# buggym2017_condensed.net
KiCad netlist of a schematic drawn in EAGLE
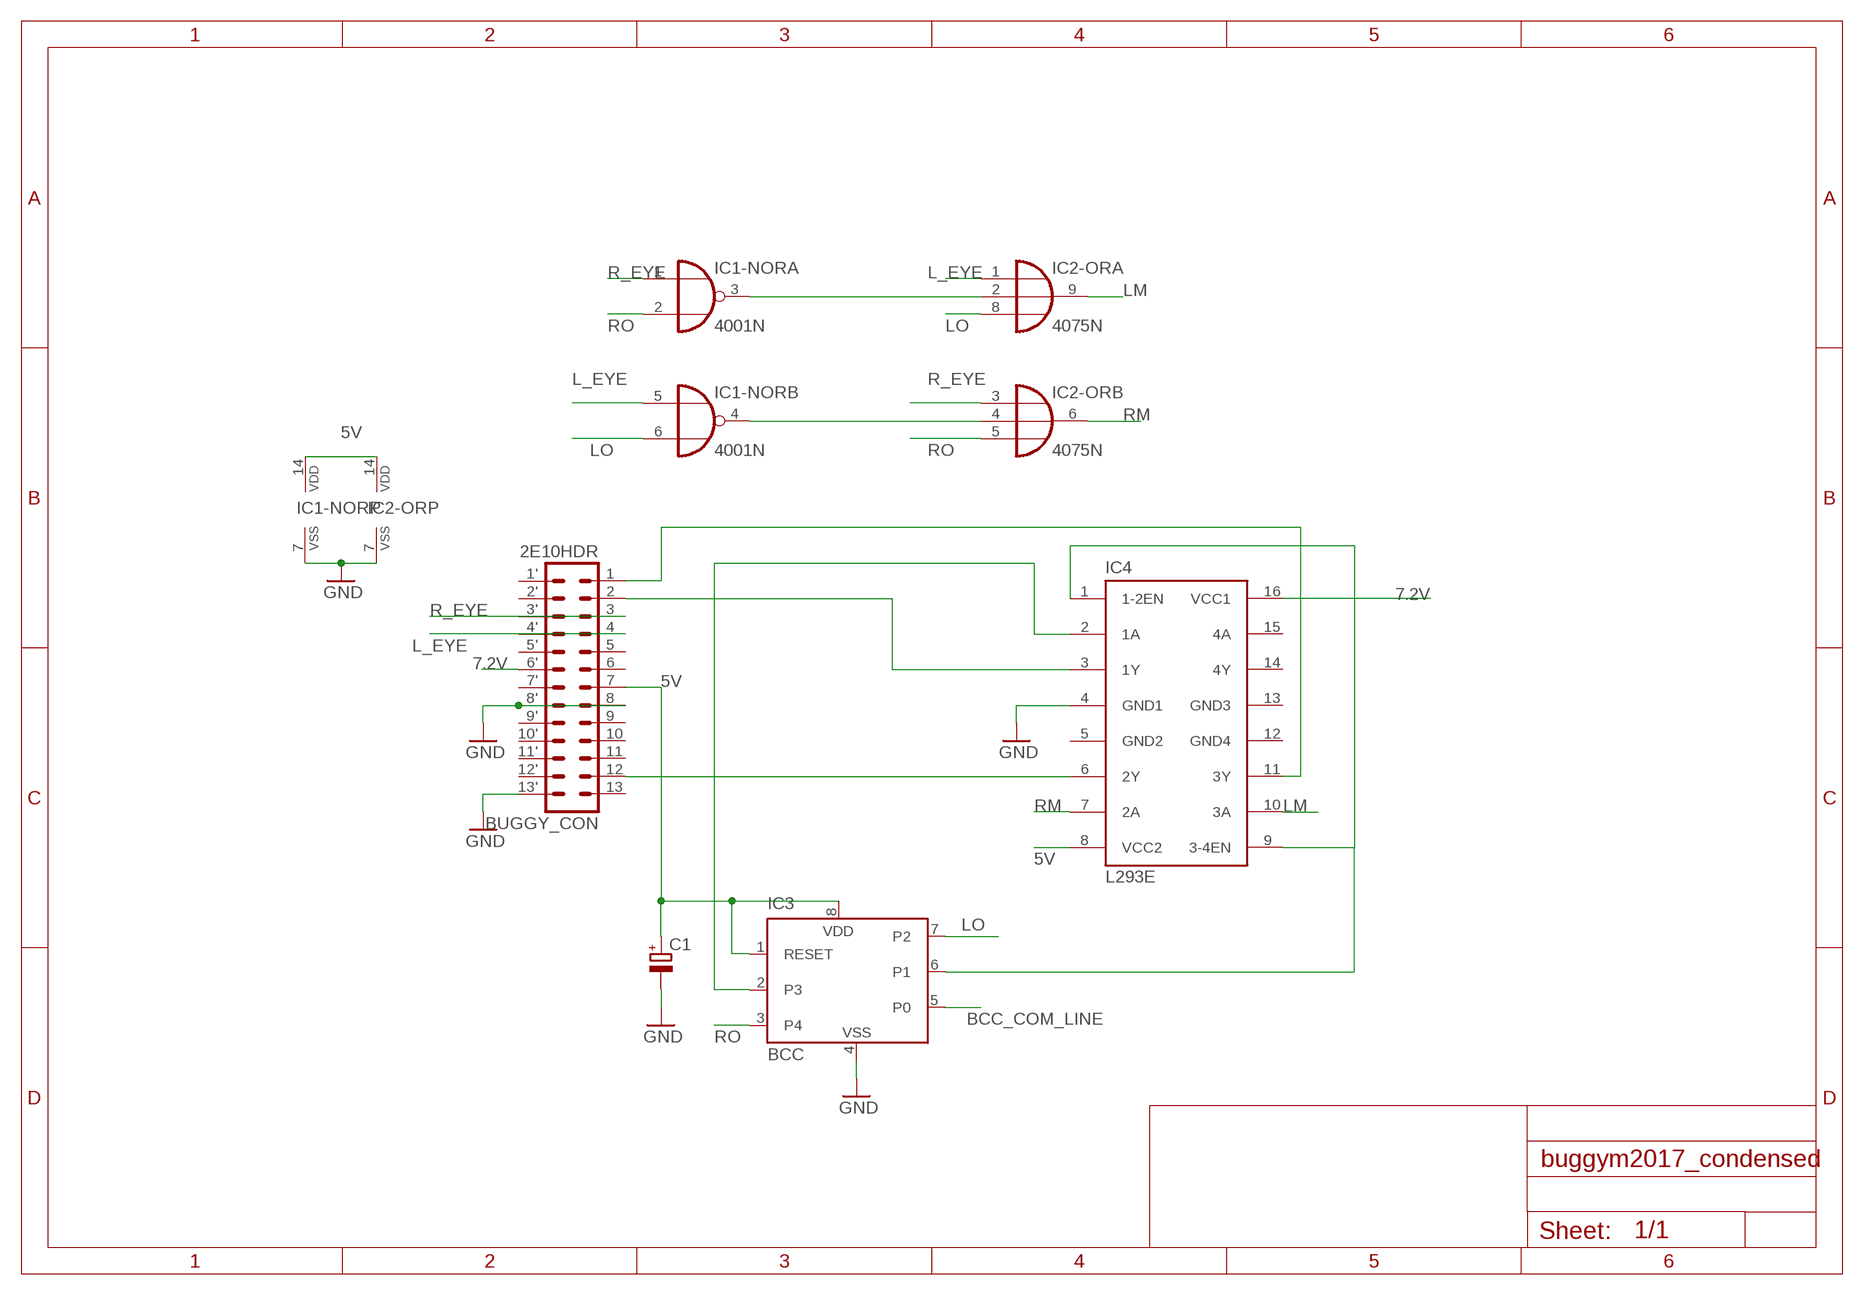
[diagram p0: schematic, sheet 1]

(export (version "E")
  (design (tool "Eeschema 10.0.6"))
  (components
    (comp (ref "BUGGY_CON")
      (value "2E10HDR")
      (footprint "eagle-import:2E10BOARD")
      (libsource (lib "eagle-import") (part "2E10HDR"))
    )
    (comp (ref "C1")
      (value "CPOL-EUE5-4")
      (footprint "eagle-import:E5-4")
      (libsource (lib "eagle-import") (part "CPOL-EUE5-4"))
    )
    (comp (ref "IC1-NOR")
      (value "4001N")
      (footprint "eagle-import:DIL14")
      (libsource (lib "eagle-import") (part "4001N"))
    )
    (comp (ref "IC2-OR")
      (value "4075N")
      (footprint "eagle-import:DIL14")
      (libsource (lib "eagle-import") (part "4075N"))
    )
    (comp (ref "IC3")
      (value "BCC")
      (footprint "eagle-import:DIL8")
      (libsource (lib "eagle-import") (part "BCC"))
    )
    (comp (ref "IC4")
      (value "L293E")
      (footprint "eagle-import:DIL16")
      (fields (field (name "MF") "Arrow Electronics"))
      (libsource (lib "eagle-import") (part "L293E"))
    )
  )
  (nets
    (net (code "1") (name "/5V") (class "Default")
      (node (ref "BUGGY_CON") (pin "7") (pinfunction "7_7") (pintype "passive"))
      (node (ref "C1") (pin "+") (pinfunction "+_+") (pintype "passive"))
      (node (ref "IC1-NOR") (pin "14") (pinfunction "VDD_14") (pintype "power_in"))
      (node (ref "IC2-OR") (pin "14") (pinfunction "VDD_14") (pintype "power_in"))
      (node (ref "IC3") (pin "1") (pinfunction "RESET_1") (pintype "bidirectional"))
      (node (ref "IC3") (pin "8") (pinfunction "5V_8") (pintype "power_in"))
      (node (ref "IC4") (pin "8") (pinfunction "VCC2_8") (pintype "power_in"))
    )
    (net (code "2") (name "/7.2V") (class "Default")
      (node (ref "BUGGY_CON") (pin "6'") (pinfunction "6'_6'") (pintype "passive"))
      (node (ref "IC4") (pin "16") (pinfunction "VCC1_16") (pintype "power_in"))
    )
    (net (code "3") (name "/BCC_COM_LINE") (class "Default")
      (node (ref "IC3") (pin "5") (pinfunction "P0_5") (pintype "bidirectional"))
    )
    (net (code "4") (name "/GND2") (class "Default")
      (node (ref "IC4") (pin "5") (pinfunction "GND2_5") (pintype "power_in"))
    )
    (net (code "5") (name "/GND3") (class "Default")
      (node (ref "IC4") (pin "13") (pinfunction "GND3_13") (pintype "power_in"))
    )
    (net (code "6") (name "/GND4") (class "Default")
      (node (ref "IC4") (pin "12") (pinfunction "GND4_12") (pintype "power_in"))
    )
    (net (code "7") (name "/LM") (class "Default")
      (node (ref "IC2-OR") (pin "9") (pinfunction "O_9") (pintype "output"))
      (node (ref "IC4") (pin "10") (pinfunction "3A_10") (pintype "input"))
    )
    (net (code "8") (name "/LO") (class "Default")
      (node (ref "IC1-NOR") (pin "6") (pinfunction "I1_6") (pintype "input"))
      (node (ref "IC2-OR") (pin "8") (pinfunction "I2_8") (pintype "input"))
      (node (ref "IC3") (pin "7") (pinfunction "P2_7") (pintype "bidirectional"))
    )
    (net (code "9") (name "/L_EYE") (class "Default")
      (node (ref "BUGGY_CON") (pin "4") (pinfunction "4_4") (pintype "passive"))
      (node (ref "BUGGY_CON") (pin "4'") (pinfunction "4'_4'") (pintype "passive"))
      (node (ref "IC1-NOR") (pin "5") (pinfunction "I0_5") (pintype "input"))
      (node (ref "IC2-OR") (pin "1") (pinfunction "I0_1") (pintype "input"))
    )
    (net (code "10") (name "/RM") (class "Default")
      (node (ref "IC2-OR") (pin "6") (pinfunction "O_6") (pintype "output"))
      (node (ref "IC4") (pin "7") (pinfunction "2A_7") (pintype "input"))
    )
    (net (code "11") (name "/RO") (class "Default")
      (node (ref "IC1-NOR") (pin "2") (pinfunction "I1_2") (pintype "input"))
      (node (ref "IC2-OR") (pin "5") (pinfunction "I2_5") (pintype "input"))
      (node (ref "IC3") (pin "3") (pinfunction "P4_3") (pintype "input"))
    )
    (net (code "12") (name "/R_EYE") (class "Default")
      (node (ref "BUGGY_CON") (pin "3") (pinfunction "3_3") (pintype "passive"))
      (node (ref "BUGGY_CON") (pin "3'") (pinfunction "3'_3'") (pintype "passive"))
      (node (ref "IC1-NOR") (pin "1") (pinfunction "I0_1") (pintype "input"))
      (node (ref "IC2-OR") (pin "3") (pinfunction "I0_3") (pintype "input"))
    )
    (net (code "13") (name "GND") (class "Default")
      (node (ref "BUGGY_CON") (pin "13'") (pinfunction "13'_13'") (pintype "passive"))
      (node (ref "BUGGY_CON") (pin "8") (pinfunction "8_8") (pintype "passive"))
      (node (ref "BUGGY_CON") (pin "8'") (pinfunction "8'_8'") (pintype "passive"))
      (node (ref "C1") (pin "-") (pinfunction "-_-") (pintype "passive"))
      (node (ref "IC1-NOR") (pin "7") (pinfunction "VSS_7") (pintype "power_in"))
      (node (ref "IC2-OR") (pin "7") (pinfunction "VSS_7") (pintype "power_in"))
      (node (ref "IC3") (pin "4") (pinfunction "VSS_4") (pintype "power_in"))
      (node (ref "IC4") (pin "4") (pinfunction "GND1_4") (pintype "power_in"))
    )
    (net (code "14") (name "Net-(IC1-NORA-O)") (class "Default")
      (node (ref "IC1-NOR") (pin "3") (pinfunction "O_3") (pintype "output"))
      (node (ref "IC2-OR") (pin "2") (pinfunction "I1_2") (pintype "input"))
    )
    (net (code "15") (name "Net-(IC1-NORB-O)") (class "Default")
      (node (ref "IC1-NOR") (pin "4") (pinfunction "O_4") (pintype "output"))
      (node (ref "IC2-OR") (pin "4") (pinfunction "I1_4") (pintype "input"))
    )
    (net (code "16") (name "Net-(IC3-P1)") (class "Default")
      (node (ref "IC3") (pin "6") (pinfunction "P1_6") (pintype "bidirectional"))
      (node (ref "IC4") (pin "1") (pinfunction "1-2EN_1") (pintype "input"))
      (node (ref "IC4") (pin "9") (pinfunction "3-4EN_9") (pintype "input"))
    )
    (net (code "17") (name "Net-(IC3-P3)") (class "Default")
      (node (ref "IC3") (pin "2") (pinfunction "P3_2") (pintype "bidirectional"))
      (node (ref "IC4") (pin "2") (pinfunction "1A_2") (pintype "input"))
    )
    (net (code "18") (name "Net-(IC4-1Y)") (class "Default")
      (node (ref "BUGGY_CON") (pin "2") (pinfunction "2_2") (pintype "passive"))
      (node (ref "IC4") (pin "3") (pinfunction "1Y_3") (pintype "output"))
    )
    (net (code "19") (name "Net-(IC4-2Y)") (class "Default")
      (node (ref "BUGGY_CON") (pin "12") (pinfunction "12_12") (pintype "passive"))
      (node (ref "IC4") (pin "6") (pinfunction "2Y_6") (pintype "output"))
    )
    (net (code "20") (name "Net-(IC4-3Y)") (class "Default")
      (node (ref "BUGGY_CON") (pin "1") (pinfunction "1_1") (pintype "passive"))
      (node (ref "IC4") (pin "11") (pinfunction "3Y_11") (pintype "output"))
    )
    (net (code "21") (name "unconnected-(BUGGY_CON-Pad1')") (class "Default")
      (node (ref "BUGGY_CON") (pin "1'") (pinfunction "1'_1'") (pintype "passive"))
    )
    (net (code "22") (name "unconnected-(BUGGY_CON-Pad2')") (class "Default")
      (node (ref "BUGGY_CON") (pin "2'") (pinfunction "2'_2'") (pintype "passive"))
    )
    (net (code "23") (name "unconnected-(BUGGY_CON-Pad5')") (class "Default")
      (node (ref "BUGGY_CON") (pin "5'") (pinfunction "5'_5'") (pintype "passive"))
    )
    (net (code "24") (name "unconnected-(BUGGY_CON-Pad5)") (class "Default")
      (node (ref "BUGGY_CON") (pin "5") (pinfunction "5_5") (pintype "passive"))
    )
    (net (code "25") (name "unconnected-(BUGGY_CON-Pad6)") (class "Default")
      (node (ref "BUGGY_CON") (pin "6") (pinfunction "6_6") (pintype "passive"))
    )
    (net (code "26") (name "unconnected-(BUGGY_CON-Pad7')") (class "Default")
      (node (ref "BUGGY_CON") (pin "7'") (pinfunction "7'_7'") (pintype "passive"))
    )
    (net (code "27") (name "unconnected-(BUGGY_CON-Pad9')") (class "Default")
      (node (ref "BUGGY_CON") (pin "9'") (pinfunction "9'_9'") (pintype "passive"))
    )
    (net (code "28") (name "unconnected-(BUGGY_CON-Pad9)") (class "Default")
      (node (ref "BUGGY_CON") (pin "9") (pinfunction "9_9") (pintype "passive"))
    )
    (net (code "29") (name "unconnected-(BUGGY_CON-Pad10')") (class "Default")
      (node (ref "BUGGY_CON") (pin "10'") (pinfunction "10'_10'") (pintype "passive"))
    )
    (net (code "30") (name "unconnected-(BUGGY_CON-Pad10)") (class "Default")
      (node (ref "BUGGY_CON") (pin "10") (pinfunction "10_10") (pintype "passive"))
    )
    (net (code "31") (name "unconnected-(BUGGY_CON-Pad11')") (class "Default")
      (node (ref "BUGGY_CON") (pin "11'") (pinfunction "11'_11'") (pintype "passive"))
    )
    (net (code "32") (name "unconnected-(BUGGY_CON-Pad11)") (class "Default")
      (node (ref "BUGGY_CON") (pin "11") (pinfunction "11_11") (pintype "passive"))
    )
    (net (code "33") (name "unconnected-(BUGGY_CON-Pad12')") (class "Default")
      (node (ref "BUGGY_CON") (pin "12'") (pinfunction "12'_12'") (pintype "passive"))
    )
    (net (code "34") (name "unconnected-(BUGGY_CON-Pad13)") (class "Default")
      (node (ref "BUGGY_CON") (pin "13") (pinfunction "13_13") (pintype "passive"))
    )
    (net (code "35") (name "unconnected-(IC4-4A-Pad15)") (class "Default")
      (node (ref "IC4") (pin "15") (pinfunction "4A_15") (pintype "input"))
    )
    (net (code "36") (name "unconnected-(IC4-4Y-Pad14)") (class "Default")
      (node (ref "IC4") (pin "14") (pinfunction "4Y_14") (pintype "output"))
    )
  )
)
